# ADC.net
KiCad netlist of a schematic drawn in Altium Designer
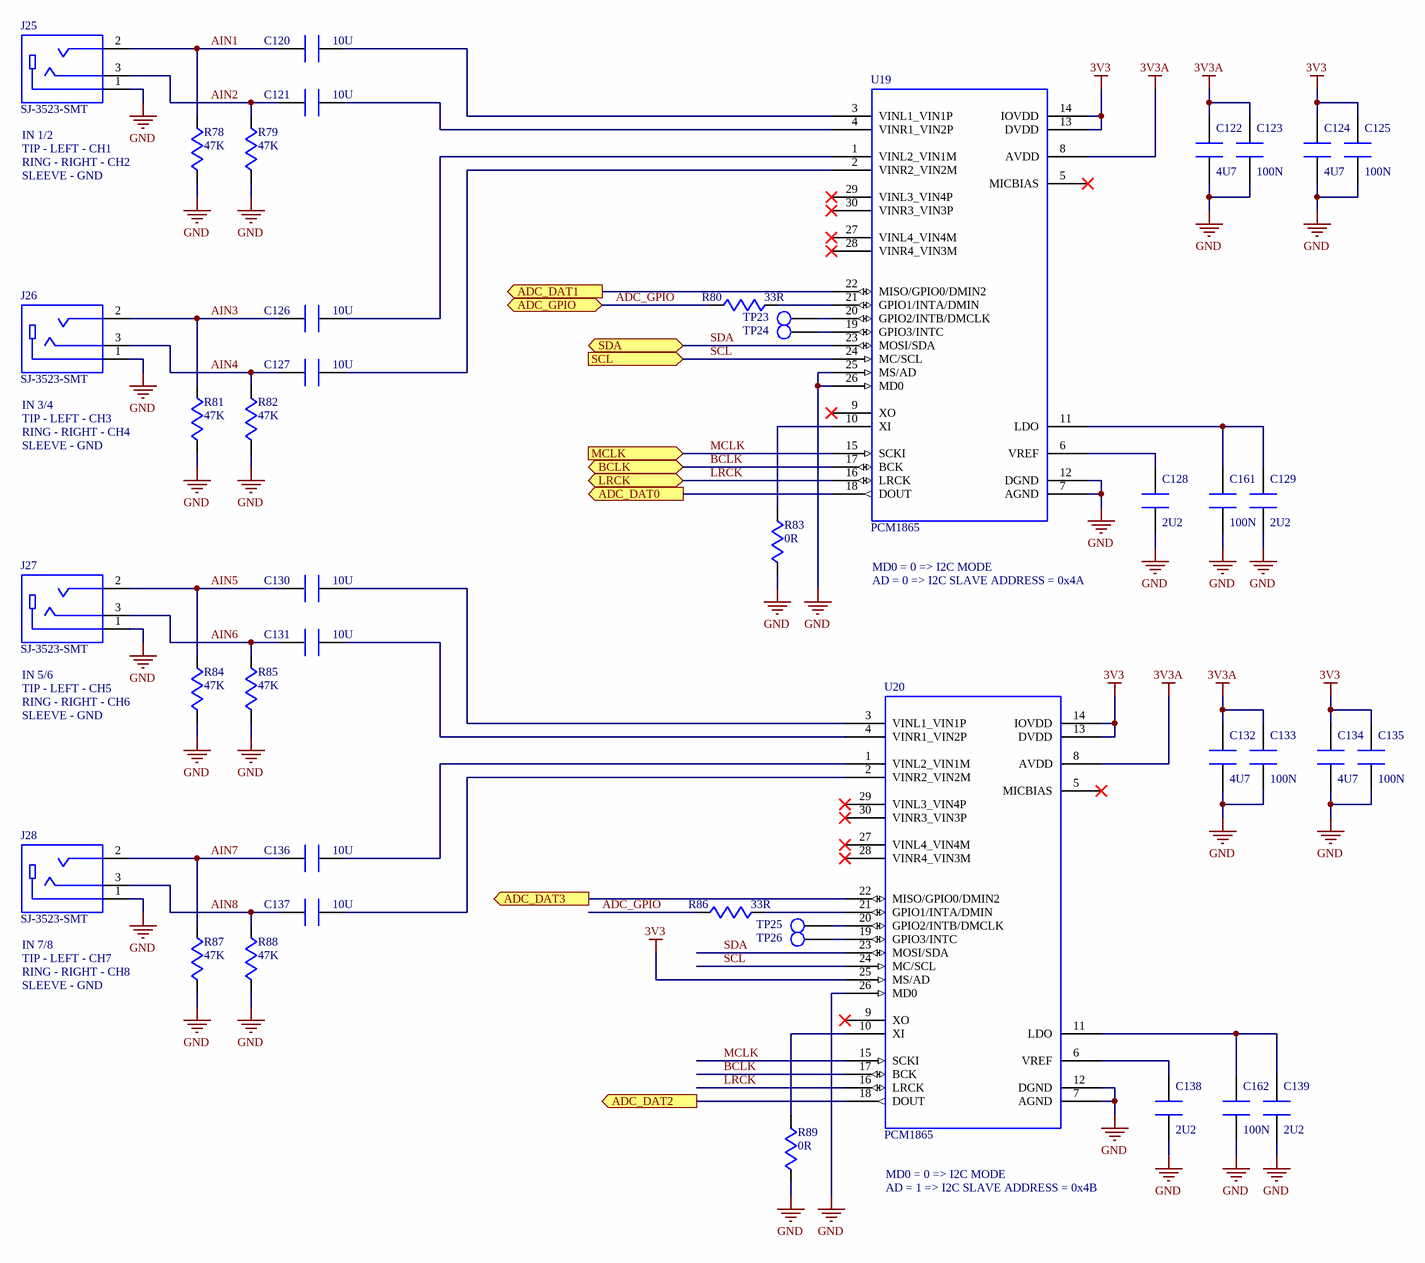
[diagram p0: ADC.SchDoc]

(export (version "E")
  (design (tool "Eeschema 10.0.6"))
  (components
    (comp (ref "C120")
      (value "10U")
      (footprint "CAPC2012X145N")
      (description "CHIP CAPACITOR, CERAMIC, 10UF, 10V, 20%, X7R, 0805")
      (fields (field (name "PART NUMBER") "GEN-03-0048") (field (name "TOLERANCE") "20%"))
      (libsource (lib "JG_GeneralLibrary") (part "CAP_NP"))
    )
    (comp (ref "C121")
      (value "10U")
      (footprint "CAPC2012X145N")
      (description "CHIP CAPACITOR, CERAMIC, 10UF, 10V, 20%, X7R, 0805")
      (fields (field (name "PART NUMBER") "GEN-03-0048") (field (name "TOLERANCE") "20%"))
      (libsource (lib "JG_GeneralLibrary") (part "CAP_NP"))
    )
    (comp (ref "C122")
      (value "4U7")
      (footprint "CAPC1608X90N")
      (description "CHIP CAPACITOR, CERAMIC, 4.7UF, 16V, 10%, X5R, 0603")
      (fields (field (name "PART NUMBER") "STD-06-0151") (field (name "TOLERANCE") "10%"))
      (libsource (lib "JG_StandardLibrary") (part "CAP_NP"))
    )
    (comp (ref "C123")
      (value "100N")
      (footprint "CAPC1005X55N")
      (description "CHIP CAPACITOR, CERAMIC, 100NF, 16V, 10%, X7R, 0402")
      (fields (field (name "PART NUMBER") "STD-06-0048") (field (name "TOLERANCE") "10%"))
      (libsource (lib "JG_StandardLibrary") (part "CAP_NP"))
    )
    (comp (ref "C124")
      (value "4U7")
      (footprint "CAPC1608X90N")
      (description "CHIP CAPACITOR, CERAMIC, 4.7UF, 16V, 10%, X5R, 0603")
      (fields (field (name "PART NUMBER") "STD-06-0151") (field (name "TOLERANCE") "10%"))
      (libsource (lib "JG_StandardLibrary") (part "CAP_NP"))
    )
    (comp (ref "C125")
      (value "100N")
      (footprint "CAPC1005X55N")
      (description "CHIP CAPACITOR, CERAMIC, 100NF, 16V, 10%, X7R, 0402")
      (fields (field (name "PART NUMBER") "STD-06-0048") (field (name "TOLERANCE") "10%"))
      (libsource (lib "JG_StandardLibrary") (part "CAP_NP"))
    )
    (comp (ref "C126")
      (value "10U")
      (footprint "CAPC2012X145N")
      (description "CHIP CAPACITOR, CERAMIC, 10UF, 10V, 20%, X7R, 0805")
      (fields (field (name "PART NUMBER") "GEN-03-0048") (field (name "TOLERANCE") "20%"))
      (libsource (lib "JG_GeneralLibrary") (part "CAP_NP"))
    )
    (comp (ref "C127")
      (value "10U")
      (footprint "CAPC2012X145N")
      (description "CHIP CAPACITOR, CERAMIC, 10UF, 10V, 20%, X7R, 0805")
      (fields (field (name "PART NUMBER") "GEN-03-0048") (field (name "TOLERANCE") "20%"))
      (libsource (lib "JG_GeneralLibrary") (part "CAP_NP"))
    )
    (comp (ref "C128")
      (value "2U2")
      (footprint "CAPC1608X90N")
      (description "CHIP CAPACITOR, CERAMIC, 2.2UF, 16V, 10%, X5R, 0603")
      (fields (field (name "PART NUMBER") "STD-06-0152") (field (name "TOLERANCE") "10%"))
      (libsource (lib "JG_StandardLibrary") (part "CAP_NP"))
    )
    (comp (ref "C129")
      (value "2U2")
      (footprint "CAPC1608X90N")
      (description "CHIP CAPACITOR, CERAMIC, 2.2UF, 16V, 10%, X5R, 0603")
      (fields (field (name "PART NUMBER") "STD-06-0152") (field (name "TOLERANCE") "10%"))
      (libsource (lib "JG_StandardLibrary") (part "CAP_NP"))
    )
    (comp (ref "C130")
      (value "10U")
      (footprint "CAPC2012X145N")
      (description "CHIP CAPACITOR, CERAMIC, 10UF, 10V, 20%, X7R, 0805")
      (fields (field (name "PART NUMBER") "GEN-03-0048") (field (name "TOLERANCE") "20%"))
      (libsource (lib "JG_GeneralLibrary") (part "CAP_NP"))
    )
    (comp (ref "C131")
      (value "10U")
      (footprint "CAPC2012X145N")
      (description "CHIP CAPACITOR, CERAMIC, 10UF, 10V, 20%, X7R, 0805")
      (fields (field (name "PART NUMBER") "GEN-03-0048") (field (name "TOLERANCE") "20%"))
      (libsource (lib "JG_GeneralLibrary") (part "CAP_NP"))
    )
    (comp (ref "C132")
      (value "4U7")
      (footprint "CAPC1608X90N")
      (description "CHIP CAPACITOR, CERAMIC, 4.7UF, 16V, 10%, X5R, 0603")
      (fields (field (name "PART NUMBER") "STD-06-0151") (field (name "TOLERANCE") "10%"))
      (libsource (lib "JG_StandardLibrary") (part "CAP_NP"))
    )
    (comp (ref "C133")
      (value "100N")
      (footprint "CAPC1005X55N")
      (description "CHIP CAPACITOR, CERAMIC, 100NF, 16V, 10%, X7R, 0402")
      (fields (field (name "PART NUMBER") "STD-06-0048") (field (name "TOLERANCE") "10%"))
      (libsource (lib "JG_StandardLibrary") (part "CAP_NP"))
    )
    (comp (ref "C134")
      (value "4U7")
      (footprint "CAPC1608X90N")
      (description "CHIP CAPACITOR, CERAMIC, 4.7UF, 16V, 10%, X5R, 0603")
      (fields (field (name "PART NUMBER") "STD-06-0151") (field (name "TOLERANCE") "10%"))
      (libsource (lib "JG_StandardLibrary") (part "CAP_NP"))
    )
    (comp (ref "C135")
      (value "100N")
      (footprint "CAPC1005X55N")
      (description "CHIP CAPACITOR, CERAMIC, 100NF, 16V, 10%, X7R, 0402")
      (fields (field (name "PART NUMBER") "STD-06-0048") (field (name "TOLERANCE") "10%"))
      (libsource (lib "JG_StandardLibrary") (part "CAP_NP"))
    )
    (comp (ref "C136")
      (value "10U")
      (footprint "CAPC2012X145N")
      (description "CHIP CAPACITOR, CERAMIC, 10UF, 10V, 20%, X7R, 0805")
      (fields (field (name "PART NUMBER") "GEN-03-0048") (field (name "TOLERANCE") "20%"))
      (libsource (lib "JG_GeneralLibrary") (part "CAP_NP"))
    )
    (comp (ref "C137")
      (value "10U")
      (footprint "CAPC2012X145N")
      (description "CHIP CAPACITOR, CERAMIC, 10UF, 10V, 20%, X7R, 0805")
      (fields (field (name "PART NUMBER") "GEN-03-0048") (field (name "TOLERANCE") "20%"))
      (libsource (lib "JG_GeneralLibrary") (part "CAP_NP"))
    )
    (comp (ref "C138")
      (value "2U2")
      (footprint "CAPC1608X90N")
      (description "CHIP CAPACITOR, CERAMIC, 2.2UF, 16V, 10%, X5R, 0603")
      (fields (field (name "PART NUMBER") "STD-06-0152") (field (name "TOLERANCE") "10%"))
      (libsource (lib "JG_StandardLibrary") (part "CAP_NP"))
    )
    (comp (ref "C139")
      (value "2U2")
      (footprint "CAPC1608X90N")
      (description "CHIP CAPACITOR, CERAMIC, 2.2UF, 16V, 10%, X5R, 0603")
      (fields (field (name "PART NUMBER") "STD-06-0152") (field (name "TOLERANCE") "10%"))
      (libsource (lib "JG_StandardLibrary") (part "CAP_NP"))
    )
    (comp (ref "C161")
      (value "100N")
      (footprint "CAPC1005X55N")
      (description "CHIP CAPACITOR, CERAMIC, 100NF, 16V, 10%, X7R, 0402")
      (fields (field (name "PART NUMBER") "STD-06-0048") (field (name "TOLERANCE") "10%"))
      (libsource (lib "JG_StandardLibrary") (part "CAP_NP"))
    )
    (comp (ref "C162")
      (value "100N")
      (footprint "CAPC1005X55N")
      (description "CHIP CAPACITOR, CERAMIC, 100NF, 16V, 10%, X7R, 0402")
      (fields (field (name "PART NUMBER") "STD-06-0048") (field (name "TOLERANCE") "10%"))
      (libsource (lib "JG_StandardLibrary") (part "CAP_NP"))
    )
    (comp (ref "J25")
      (value "SJ-3523-SMT")
      (footprint "CON_CUI_SJ3523")
      (description "TRS jack, 3.5mm, SMD")
      (fields (field (name "PART NUMBER") "GEN-01-0021") (field (name "MANUFACTURER") "CUI"))
      (libsource (lib "JG_GeneralLibrary") (part "TRS_JACK_3_A"))
    )
    (comp (ref "J26")
      (value "SJ-3523-SMT")
      (footprint "CON_CUI_SJ3523")
      (description "TRS jack, 3.5mm, SMD")
      (fields (field (name "PART NUMBER") "GEN-01-0021") (field (name "MANUFACTURER") "CUI"))
      (libsource (lib "JG_GeneralLibrary") (part "TRS_JACK_3_A"))
    )
    (comp (ref "J27")
      (value "SJ-3523-SMT")
      (footprint "CON_CUI_SJ3523")
      (description "TRS jack, 3.5mm, SMD")
      (fields (field (name "PART NUMBER") "GEN-01-0021") (field (name "MANUFACTURER") "CUI"))
      (libsource (lib "JG_GeneralLibrary") (part "TRS_JACK_3_A"))
    )
    (comp (ref "J28")
      (value "SJ-3523-SMT")
      (footprint "CON_CUI_SJ3523")
      (description "TRS jack, 3.5mm, SMD")
      (fields (field (name "PART NUMBER") "GEN-01-0021") (field (name "MANUFACTURER") "CUI"))
      (libsource (lib "JG_GeneralLibrary") (part "TRS_JACK_3_A"))
    )
    (comp (ref "R78")
      (value "47K")
      (footprint "RESC1608X55N")
      (description "CHIP RESISTOR, 47K OHM, 0.1W, 1%, 0603")
      (fields (field (name "PART NUMBER") "STD-02-0102") (field (name "TOLERANCE") "1%"))
      (libsource (lib "JG_StandardLibrary") (part "RES"))
    )
    (comp (ref "R79")
      (value "47K")
      (footprint "RESC1608X55N")
      (description "CHIP RESISTOR, 47K OHM, 0.1W, 1%, 0603")
      (fields (field (name "PART NUMBER") "STD-02-0102") (field (name "TOLERANCE") "1%"))
      (libsource (lib "JG_StandardLibrary") (part "RES"))
    )
    (comp (ref "R80")
      (value "33R")
      (footprint "RESC1608X55N")
      (description "CHIP RESISTOR, 33 OHM, 0.1W, 1%, 0603")
      (fields (field (name "PART NUMBER") "STD-02-0026") (field (name "TOLERANCE") "1%"))
      (libsource (lib "JG_StandardLibrary") (part "RES"))
    )
    (comp (ref "R81")
      (value "47K")
      (footprint "RESC1608X55N")
      (description "CHIP RESISTOR, 47K OHM, 0.1W, 1%, 0603")
      (fields (field (name "PART NUMBER") "STD-02-0102") (field (name "TOLERANCE") "1%"))
      (libsource (lib "JG_StandardLibrary") (part "RES"))
    )
    (comp (ref "R82")
      (value "47K")
      (footprint "RESC1608X55N")
      (description "CHIP RESISTOR, 47K OHM, 0.1W, 1%, 0603")
      (fields (field (name "PART NUMBER") "STD-02-0102") (field (name "TOLERANCE") "1%"))
      (libsource (lib "JG_StandardLibrary") (part "RES"))
    )
    (comp (ref "R83")
      (value "0R")
      (footprint "RESC1608X55N")
      (description "CHIP RESISTOR, ZERO OHM JUMPER, 1A, 0603")
      (fields (field (name "PART NUMBER") "STD-02-0001") (field (name "TOLERANCE") "NA"))
      (libsource (lib "JG_StandardLibrary") (part "RES"))
    )
    (comp (ref "R84")
      (value "47K")
      (footprint "RESC1608X55N")
      (description "CHIP RESISTOR, 47K OHM, 0.1W, 1%, 0603")
      (fields (field (name "PART NUMBER") "STD-02-0102") (field (name "TOLERANCE") "1%"))
      (libsource (lib "JG_StandardLibrary") (part "RES"))
    )
    (comp (ref "R85")
      (value "47K")
      (footprint "RESC1608X55N")
      (description "CHIP RESISTOR, 47K OHM, 0.1W, 1%, 0603")
      (fields (field (name "PART NUMBER") "STD-02-0102") (field (name "TOLERANCE") "1%"))
      (libsource (lib "JG_StandardLibrary") (part "RES"))
    )
    (comp (ref "R86")
      (value "33R")
      (footprint "RESC1608X55N")
      (description "CHIP RESISTOR, 33 OHM, 0.1W, 1%, 0603")
      (fields (field (name "PART NUMBER") "STD-02-0026") (field (name "TOLERANCE") "1%"))
      (libsource (lib "JG_StandardLibrary") (part "RES"))
    )
    (comp (ref "R87")
      (value "47K")
      (footprint "RESC1608X55N")
      (description "CHIP RESISTOR, 47K OHM, 0.1W, 1%, 0603")
      (fields (field (name "PART NUMBER") "STD-02-0102") (field (name "TOLERANCE") "1%"))
      (libsource (lib "JG_StandardLibrary") (part "RES"))
    )
    (comp (ref "R88")
      (value "47K")
      (footprint "RESC1608X55N")
      (description "CHIP RESISTOR, 47K OHM, 0.1W, 1%, 0603")
      (fields (field (name "PART NUMBER") "STD-02-0102") (field (name "TOLERANCE") "1%"))
      (libsource (lib "JG_StandardLibrary") (part "RES"))
    )
    (comp (ref "R89")
      (value "0R")
      (footprint "RESC1608X55N")
      (description "CHIP RESISTOR, ZERO OHM JUMPER, 1A, 0603")
      (fields (field (name "PART NUMBER") "STD-02-0001") (field (name "TOLERANCE") "NA"))
      (libsource (lib "JG_StandardLibrary") (part "RES"))
    )
    (comp (ref "TP23")
      (value "TESTPOINT")
      (footprint "TESTPOINT_SMD_1MM")
      (description "Testpoint, SMD, 1mm")
      (fields (field (name "PART NUMBER") "GEN-24-0003") (field (name "MANUFACTURER") "NA"))
      (libsource (lib "JG_GeneralLibrary") (part "TESTPOINT"))
    )
    (comp (ref "TP24")
      (value "TESTPOINT")
      (footprint "TESTPOINT_SMD_1MM")
      (description "Testpoint, SMD, 1mm")
      (fields (field (name "PART NUMBER") "GEN-24-0003") (field (name "MANUFACTURER") "NA"))
      (libsource (lib "JG_GeneralLibrary") (part "TESTPOINT"))
    )
    (comp (ref "TP25")
      (value "TESTPOINT")
      (footprint "TESTPOINT_SMD_1MM")
      (description "Testpoint, SMD, 1mm")
      (fields (field (name "PART NUMBER") "GEN-24-0003") (field (name "MANUFACTURER") "NA"))
      (libsource (lib "JG_GeneralLibrary") (part "TESTPOINT"))
    )
    (comp (ref "TP26")
      (value "TESTPOINT")
      (footprint "TESTPOINT_SMD_1MM")
      (description "Testpoint, SMD, 1mm")
      (fields (field (name "PART NUMBER") "GEN-24-0003") (field (name "MANUFACTURER") "NA"))
      (libsource (lib "JG_GeneralLibrary") (part "TESTPOINT"))
    )
    (comp (ref "U19")
      (value "PCM1865")
      (footprint "SOP30P50_780X640X120L62X20N")
      (fields
        (field (name "PART NUMBER") "GEN-06-0022")
        (field (name "MANUFACTURER") "Texas Instruments")
        (field (name "MANUFACTURER PART NUMBER") "PCM1865DBTR")
      )
      (libsource (lib "JG_GeneralLibrary") (part "TI_PCM1865"))
    )
    (comp (ref "U20")
      (value "PCM1865")
      (footprint "SOP30P50_780X640X120L62X20N")
      (fields
        (field (name "PART NUMBER") "GEN-06-0022")
        (field (name "MANUFACTURER") "Texas Instruments")
        (field (name "MANUFACTURER PART NUMBER") "PCM1865DBTR")
      )
      (libsource (lib "JG_GeneralLibrary") (part "TI_PCM1865"))
    )
  )
  (nets
    (net (code "1") (name "/ADC_DAT0") (class "Default")
      (node (ref "U19") (pin "18") (pinfunction "DOUT_18") (pintype "output"))
    )
    (net (code "2") (name "/ADC_DAT1") (class "Default")
      (node (ref "U19") (pin "22") (pinfunction "MISO/GPIO0/DMIN2_22") (pintype "bidirectional"))
    )
    (net (code "3") (name "/ADC_DAT2") (class "Default")
      (node (ref "U20") (pin "18") (pinfunction "DOUT_18") (pintype "output"))
    )
    (net (code "4") (name "/ADC_DAT3") (class "Default")
      (node (ref "U20") (pin "22") (pinfunction "MISO/GPIO0/DMIN2_22") (pintype "bidirectional"))
    )
    (net (code "5") (name "/ADC_GPIO") (class "Default")
      (node (ref "R80") (pin "1") (pinfunction "1_1") (pintype "passive"))
      (node (ref "R86") (pin "1") (pinfunction "1_1") (pintype "passive"))
    )
    (net (code "6") (name "/AIN1") (class "Default")
      (node (ref "C120") (pin "1") (pinfunction "1_1") (pintype "passive"))
      (node (ref "J25") (pin "2") (pinfunction "2_2") (pintype "passive"))
      (node (ref "R78") (pin "2") (pinfunction "2_2") (pintype "passive"))
    )
    (net (code "7") (name "/AIN2") (class "Default")
      (node (ref "C121") (pin "1") (pinfunction "1_1") (pintype "passive"))
      (node (ref "J25") (pin "3") (pinfunction "3_3") (pintype "passive"))
      (node (ref "R79") (pin "2") (pinfunction "2_2") (pintype "passive"))
    )
    (net (code "8") (name "/AIN3") (class "Default")
      (node (ref "C126") (pin "1") (pinfunction "1_1") (pintype "passive"))
      (node (ref "J26") (pin "2") (pinfunction "2_2") (pintype "passive"))
      (node (ref "R81") (pin "2") (pinfunction "2_2") (pintype "passive"))
    )
    (net (code "9") (name "/AIN4") (class "Default")
      (node (ref "C127") (pin "1") (pinfunction "1_1") (pintype "passive"))
      (node (ref "J26") (pin "3") (pinfunction "3_3") (pintype "passive"))
      (node (ref "R82") (pin "2") (pinfunction "2_2") (pintype "passive"))
    )
    (net (code "10") (name "/AIN5") (class "Default")
      (node (ref "C130") (pin "1") (pinfunction "1_1") (pintype "passive"))
      (node (ref "J27") (pin "2") (pinfunction "2_2") (pintype "passive"))
      (node (ref "R84") (pin "2") (pinfunction "2_2") (pintype "passive"))
    )
    (net (code "11") (name "/AIN6") (class "Default")
      (node (ref "C131") (pin "1") (pinfunction "1_1") (pintype "passive"))
      (node (ref "J27") (pin "3") (pinfunction "3_3") (pintype "passive"))
      (node (ref "R85") (pin "2") (pinfunction "2_2") (pintype "passive"))
    )
    (net (code "12") (name "/AIN7") (class "Default")
      (node (ref "C136") (pin "1") (pinfunction "1_1") (pintype "passive"))
      (node (ref "J28") (pin "2") (pinfunction "2_2") (pintype "passive"))
      (node (ref "R87") (pin "2") (pinfunction "2_2") (pintype "passive"))
    )
    (net (code "13") (name "/AIN8") (class "Default")
      (node (ref "C137") (pin "1") (pinfunction "1_1") (pintype "passive"))
      (node (ref "J28") (pin "3") (pinfunction "3_3") (pintype "passive"))
      (node (ref "R88") (pin "2") (pinfunction "2_2") (pintype "passive"))
    )
    (net (code "14") (name "/BCLK") (class "Default")
      (node (ref "U19") (pin "17") (pinfunction "BCK_17") (pintype "bidirectional"))
      (node (ref "U20") (pin "17") (pinfunction "BCK_17") (pintype "bidirectional"))
    )
    (net (code "15") (name "/LRCK") (class "Default")
      (node (ref "U19") (pin "16") (pinfunction "LRCK_16") (pintype "bidirectional"))
      (node (ref "U20") (pin "16") (pinfunction "LRCK_16") (pintype "bidirectional"))
    )
    (net (code "16") (name "/MCLK") (class "Default")
      (node (ref "U19") (pin "15") (pinfunction "SCKI_15") (pintype "input"))
      (node (ref "U20") (pin "15") (pinfunction "SCKI_15") (pintype "input"))
    )
    (net (code "17") (name "/SCL") (class "Default")
      (node (ref "U19") (pin "24") (pinfunction "MC/SCL_24") (pintype "input"))
      (node (ref "U20") (pin "24") (pinfunction "MC/SCL_24") (pintype "input"))
    )
    (net (code "18") (name "/SDA") (class "Default")
      (node (ref "U19") (pin "23") (pinfunction "MOSI/SDA_23") (pintype "bidirectional"))
      (node (ref "U20") (pin "23") (pinfunction "MOSI/SDA_23") (pintype "bidirectional"))
    )
    (net (code "19") (name "3V3") (class "Default")
      (node (ref "C124") (pin "1") (pinfunction "1_1") (pintype "passive"))
      (node (ref "C125") (pin "1") (pinfunction "1_1") (pintype "passive"))
      (node (ref "C134") (pin "1") (pinfunction "1_1") (pintype "passive"))
      (node (ref "C135") (pin "1") (pinfunction "1_1") (pintype "passive"))
      (node (ref "U19") (pin "13") (pinfunction "DVDD_13") (pintype "power_in"))
      (node (ref "U19") (pin "14") (pinfunction "IOVDD_14") (pintype "power_in"))
      (node (ref "U20") (pin "13") (pinfunction "DVDD_13") (pintype "power_in"))
      (node (ref "U20") (pin "14") (pinfunction "IOVDD_14") (pintype "power_in"))
      (node (ref "U20") (pin "25") (pinfunction "MS/AD_25") (pintype "input"))
    )
    (net (code "20") (name "3V3A") (class "Default")
      (node (ref "C122") (pin "1") (pinfunction "1_1") (pintype "passive"))
      (node (ref "C123") (pin "1") (pinfunction "1_1") (pintype "passive"))
      (node (ref "C132") (pin "1") (pinfunction "1_1") (pintype "passive"))
      (node (ref "C133") (pin "1") (pinfunction "1_1") (pintype "passive"))
      (node (ref "U19") (pin "8") (pinfunction "AVDD_8") (pintype "power_in"))
      (node (ref "U20") (pin "8") (pinfunction "AVDD_8") (pintype "power_in"))
    )
    (net (code "21") (name "GND") (class "Default")
      (node (ref "C122") (pin "2") (pinfunction "2_2") (pintype "passive"))
      (node (ref "C123") (pin "2") (pinfunction "2_2") (pintype "passive"))
      (node (ref "C124") (pin "2") (pinfunction "2_2") (pintype "passive"))
      (node (ref "C125") (pin "2") (pinfunction "2_2") (pintype "passive"))
      (node (ref "C128") (pin "2") (pinfunction "2_2") (pintype "passive"))
      (node (ref "C129") (pin "2") (pinfunction "2_2") (pintype "passive"))
      (node (ref "C132") (pin "2") (pinfunction "2_2") (pintype "passive"))
      (node (ref "C133") (pin "2") (pinfunction "2_2") (pintype "passive"))
      (node (ref "C134") (pin "2") (pinfunction "2_2") (pintype "passive"))
      (node (ref "C135") (pin "2") (pinfunction "2_2") (pintype "passive"))
      (node (ref "C138") (pin "2") (pinfunction "2_2") (pintype "passive"))
      (node (ref "C139") (pin "2") (pinfunction "2_2") (pintype "passive"))
      (node (ref "C161") (pin "2") (pinfunction "2_2") (pintype "passive"))
      (node (ref "C162") (pin "2") (pinfunction "2_2") (pintype "passive"))
      (node (ref "J25") (pin "1") (pinfunction "1_1") (pintype "passive"))
      (node (ref "J26") (pin "1") (pinfunction "1_1") (pintype "passive"))
      (node (ref "J27") (pin "1") (pinfunction "1_1") (pintype "passive"))
      (node (ref "J28") (pin "1") (pinfunction "1_1") (pintype "passive"))
      (node (ref "R78") (pin "1") (pinfunction "1_1") (pintype "passive"))
      (node (ref "R79") (pin "1") (pinfunction "1_1") (pintype "passive"))
      (node (ref "R81") (pin "1") (pinfunction "1_1") (pintype "passive"))
      (node (ref "R82") (pin "1") (pinfunction "1_1") (pintype "passive"))
      (node (ref "R83") (pin "2") (pinfunction "2_2") (pintype "passive"))
      (node (ref "R84") (pin "1") (pinfunction "1_1") (pintype "passive"))
      (node (ref "R85") (pin "1") (pinfunction "1_1") (pintype "passive"))
      (node (ref "R87") (pin "1") (pinfunction "1_1") (pintype "passive"))
      (node (ref "R88") (pin "1") (pinfunction "1_1") (pintype "passive"))
      (node (ref "R89") (pin "2") (pinfunction "2_2") (pintype "passive"))
      (node (ref "U19") (pin "12") (pinfunction "DGND_12") (pintype "power_in"))
      (node (ref "U19") (pin "25") (pinfunction "MS/AD_25") (pintype "input"))
      (node (ref "U19") (pin "26") (pinfunction "MD0_26") (pintype "input"))
      (node (ref "U19") (pin "7") (pinfunction "AGND_7") (pintype "power_in"))
      (node (ref "U20") (pin "12") (pinfunction "DGND_12") (pintype "power_in"))
      (node (ref "U20") (pin "26") (pinfunction "MD0_26") (pintype "input"))
      (node (ref "U20") (pin "7") (pinfunction "AGND_7") (pintype "power_in"))
    )
    (net (code "22") (name "Net-(U19-GPIO1{slash}INTA{slash}DMIN)") (class "Default")
      (node (ref "R80") (pin "2") (pinfunction "2_2") (pintype "passive"))
      (node (ref "U19") (pin "21") (pinfunction "GPIO1/INTA/DMIN_21") (pintype "bidirectional"))
    )
    (net (code "23") (name "Net-(U19-GPIO2{slash}INTB{slash}DMCLK)") (class "Default")
      (node (ref "TP23") (pin "1") (pinfunction "1_1") (pintype "passive"))
      (node (ref "U19") (pin "20") (pinfunction "GPIO2/INTB/DMCLK_20") (pintype "bidirectional"))
    )
    (net (code "24") (name "Net-(U19-GPIO3{slash}INTC)") (class "Default")
      (node (ref "TP24") (pin "1") (pinfunction "1_1") (pintype "passive"))
      (node (ref "U19") (pin "19") (pinfunction "GPIO3/INTC_19") (pintype "bidirectional"))
    )
    (net (code "25") (name "Net-(U19-LDO)") (class "Default")
      (node (ref "C129") (pin "1") (pinfunction "1_1") (pintype "passive"))
      (node (ref "C161") (pin "1") (pinfunction "1_1") (pintype "passive"))
      (node (ref "U19") (pin "11") (pinfunction "LDO_11") (pintype "passive"))
    )
    (net (code "26") (name "Net-(U19-VINL1_VIN1P)") (class "Default")
      (node (ref "C120") (pin "2") (pinfunction "2_2") (pintype "passive"))
      (node (ref "U19") (pin "3") (pinfunction "VINL1_VIN1P_3") (pintype "passive"))
    )
    (net (code "27") (name "Net-(U19-VINL2_VIN1M)") (class "Default")
      (node (ref "C126") (pin "2") (pinfunction "2_2") (pintype "passive"))
      (node (ref "U19") (pin "1") (pinfunction "VINL2_VIN1M_1") (pintype "passive"))
    )
    (net (code "28") (name "Net-(U19-VINR1_VIN2P)") (class "Default")
      (node (ref "C121") (pin "2") (pinfunction "2_2") (pintype "passive"))
      (node (ref "U19") (pin "4") (pinfunction "VINR1_VIN2P_4") (pintype "passive"))
    )
    (net (code "29") (name "Net-(U19-VINR2_VIN2M)") (class "Default")
      (node (ref "C127") (pin "2") (pinfunction "2_2") (pintype "passive"))
      (node (ref "U19") (pin "2") (pinfunction "VINR2_VIN2M_2") (pintype "passive"))
    )
    (net (code "30") (name "Net-(U19-VREF)") (class "Default")
      (node (ref "C128") (pin "1") (pinfunction "1_1") (pintype "passive"))
      (node (ref "U19") (pin "6") (pinfunction "VREF_6") (pintype "passive"))
    )
    (net (code "31") (name "Net-(U19-XI)") (class "Default")
      (node (ref "R83") (pin "1") (pinfunction "1_1") (pintype "passive"))
      (node (ref "U19") (pin "10") (pinfunction "XI_10") (pintype "passive"))
    )
    (net (code "32") (name "Net-(U20-GPIO1{slash}INTA{slash}DMIN)") (class "Default")
      (node (ref "R86") (pin "2") (pinfunction "2_2") (pintype "passive"))
      (node (ref "U20") (pin "21") (pinfunction "GPIO1/INTA/DMIN_21") (pintype "bidirectional"))
    )
    (net (code "33") (name "Net-(U20-GPIO2{slash}INTB{slash}DMCLK)") (class "Default")
      (node (ref "TP25") (pin "1") (pinfunction "1_1") (pintype "passive"))
      (node (ref "U20") (pin "20") (pinfunction "GPIO2/INTB/DMCLK_20") (pintype "bidirectional"))
    )
    (net (code "34") (name "Net-(U20-GPIO3{slash}INTC)") (class "Default")
      (node (ref "TP26") (pin "1") (pinfunction "1_1") (pintype "passive"))
      (node (ref "U20") (pin "19") (pinfunction "GPIO3/INTC_19") (pintype "bidirectional"))
    )
    (net (code "35") (name "Net-(U20-LDO)") (class "Default")
      (node (ref "C139") (pin "1") (pinfunction "1_1") (pintype "passive"))
      (node (ref "C162") (pin "1") (pinfunction "1_1") (pintype "passive"))
      (node (ref "U20") (pin "11") (pinfunction "LDO_11") (pintype "passive"))
    )
    (net (code "36") (name "Net-(U20-VINL1_VIN1P)") (class "Default")
      (node (ref "C130") (pin "2") (pinfunction "2_2") (pintype "passive"))
      (node (ref "U20") (pin "3") (pinfunction "VINL1_VIN1P_3") (pintype "passive"))
    )
    (net (code "37") (name "Net-(U20-VINL2_VIN1M)") (class "Default")
      (node (ref "C136") (pin "2") (pinfunction "2_2") (pintype "passive"))
      (node (ref "U20") (pin "1") (pinfunction "VINL2_VIN1M_1") (pintype "passive"))
    )
    (net (code "38") (name "Net-(U20-VINR1_VIN2P)") (class "Default")
      (node (ref "C131") (pin "2") (pinfunction "2_2") (pintype "passive"))
      (node (ref "U20") (pin "4") (pinfunction "VINR1_VIN2P_4") (pintype "passive"))
    )
    (net (code "39") (name "Net-(U20-VINR2_VIN2M)") (class "Default")
      (node (ref "C137") (pin "2") (pinfunction "2_2") (pintype "passive"))
      (node (ref "U20") (pin "2") (pinfunction "VINR2_VIN2M_2") (pintype "passive"))
    )
    (net (code "40") (name "Net-(U20-VREF)") (class "Default")
      (node (ref "C138") (pin "1") (pinfunction "1_1") (pintype "passive"))
      (node (ref "U20") (pin "6") (pinfunction "VREF_6") (pintype "passive"))
    )
    (net (code "41") (name "Net-(U20-XI)") (class "Default")
      (node (ref "R89") (pin "1") (pinfunction "1_1") (pintype "passive"))
      (node (ref "U20") (pin "10") (pinfunction "XI_10") (pintype "passive"))
    )
    (net (code "42") (name "unconnected-(U19-MICBIAS-Pad5)") (class "Default")
      (node (ref "U19") (pin "5") (pinfunction "MICBIAS_5") (pintype "passive+no_connect"))
    )
    (net (code "43") (name "unconnected-(U19-VINL3_VIN4P-Pad29)") (class "Default")
      (node (ref "U19") (pin "29") (pinfunction "VINL3_VIN4P_29") (pintype "passive+no_connect"))
    )
    (net (code "44") (name "unconnected-(U19-VINL4_VIN4M-Pad27)") (class "Default")
      (node (ref "U19") (pin "27") (pinfunction "VINL4_VIN4M_27") (pintype "passive+no_connect"))
    )
    (net (code "45") (name "unconnected-(U19-VINR3_VIN3P-Pad30)") (class "Default")
      (node (ref "U19") (pin "30") (pinfunction "VINR3_VIN3P_30") (pintype "passive+no_connect"))
    )
    (net (code "46") (name "unconnected-(U19-VINR4_VIN3M-Pad28)") (class "Default")
      (node (ref "U19") (pin "28") (pinfunction "VINR4_VIN3M_28") (pintype "passive+no_connect"))
    )
    (net (code "47") (name "unconnected-(U19-XO-Pad9)") (class "Default")
      (node (ref "U19") (pin "9") (pinfunction "XO_9") (pintype "passive+no_connect"))
    )
    (net (code "48") (name "unconnected-(U20-MICBIAS-Pad5)") (class "Default")
      (node (ref "U20") (pin "5") (pinfunction "MICBIAS_5") (pintype "passive+no_connect"))
    )
    (net (code "49") (name "unconnected-(U20-VINL3_VIN4P-Pad29)") (class "Default")
      (node (ref "U20") (pin "29") (pinfunction "VINL3_VIN4P_29") (pintype "passive+no_connect"))
    )
    (net (code "50") (name "unconnected-(U20-VINL4_VIN4M-Pad27)") (class "Default")
      (node (ref "U20") (pin "27") (pinfunction "VINL4_VIN4M_27") (pintype "passive+no_connect"))
    )
    (net (code "51") (name "unconnected-(U20-VINR3_VIN3P-Pad30)") (class "Default")
      (node (ref "U20") (pin "30") (pinfunction "VINR3_VIN3P_30") (pintype "passive+no_connect"))
    )
    (net (code "52") (name "unconnected-(U20-VINR4_VIN3M-Pad28)") (class "Default")
      (node (ref "U20") (pin "28") (pinfunction "VINR4_VIN3M_28") (pintype "passive+no_connect"))
    )
    (net (code "53") (name "unconnected-(U20-XO-Pad9)") (class "Default")
      (node (ref "U20") (pin "9") (pinfunction "XO_9") (pintype "passive+no_connect"))
    )
  )
)
